# Micro_RC_Transmitter.net
KiCad netlist of a schematic drawn in EAGLE
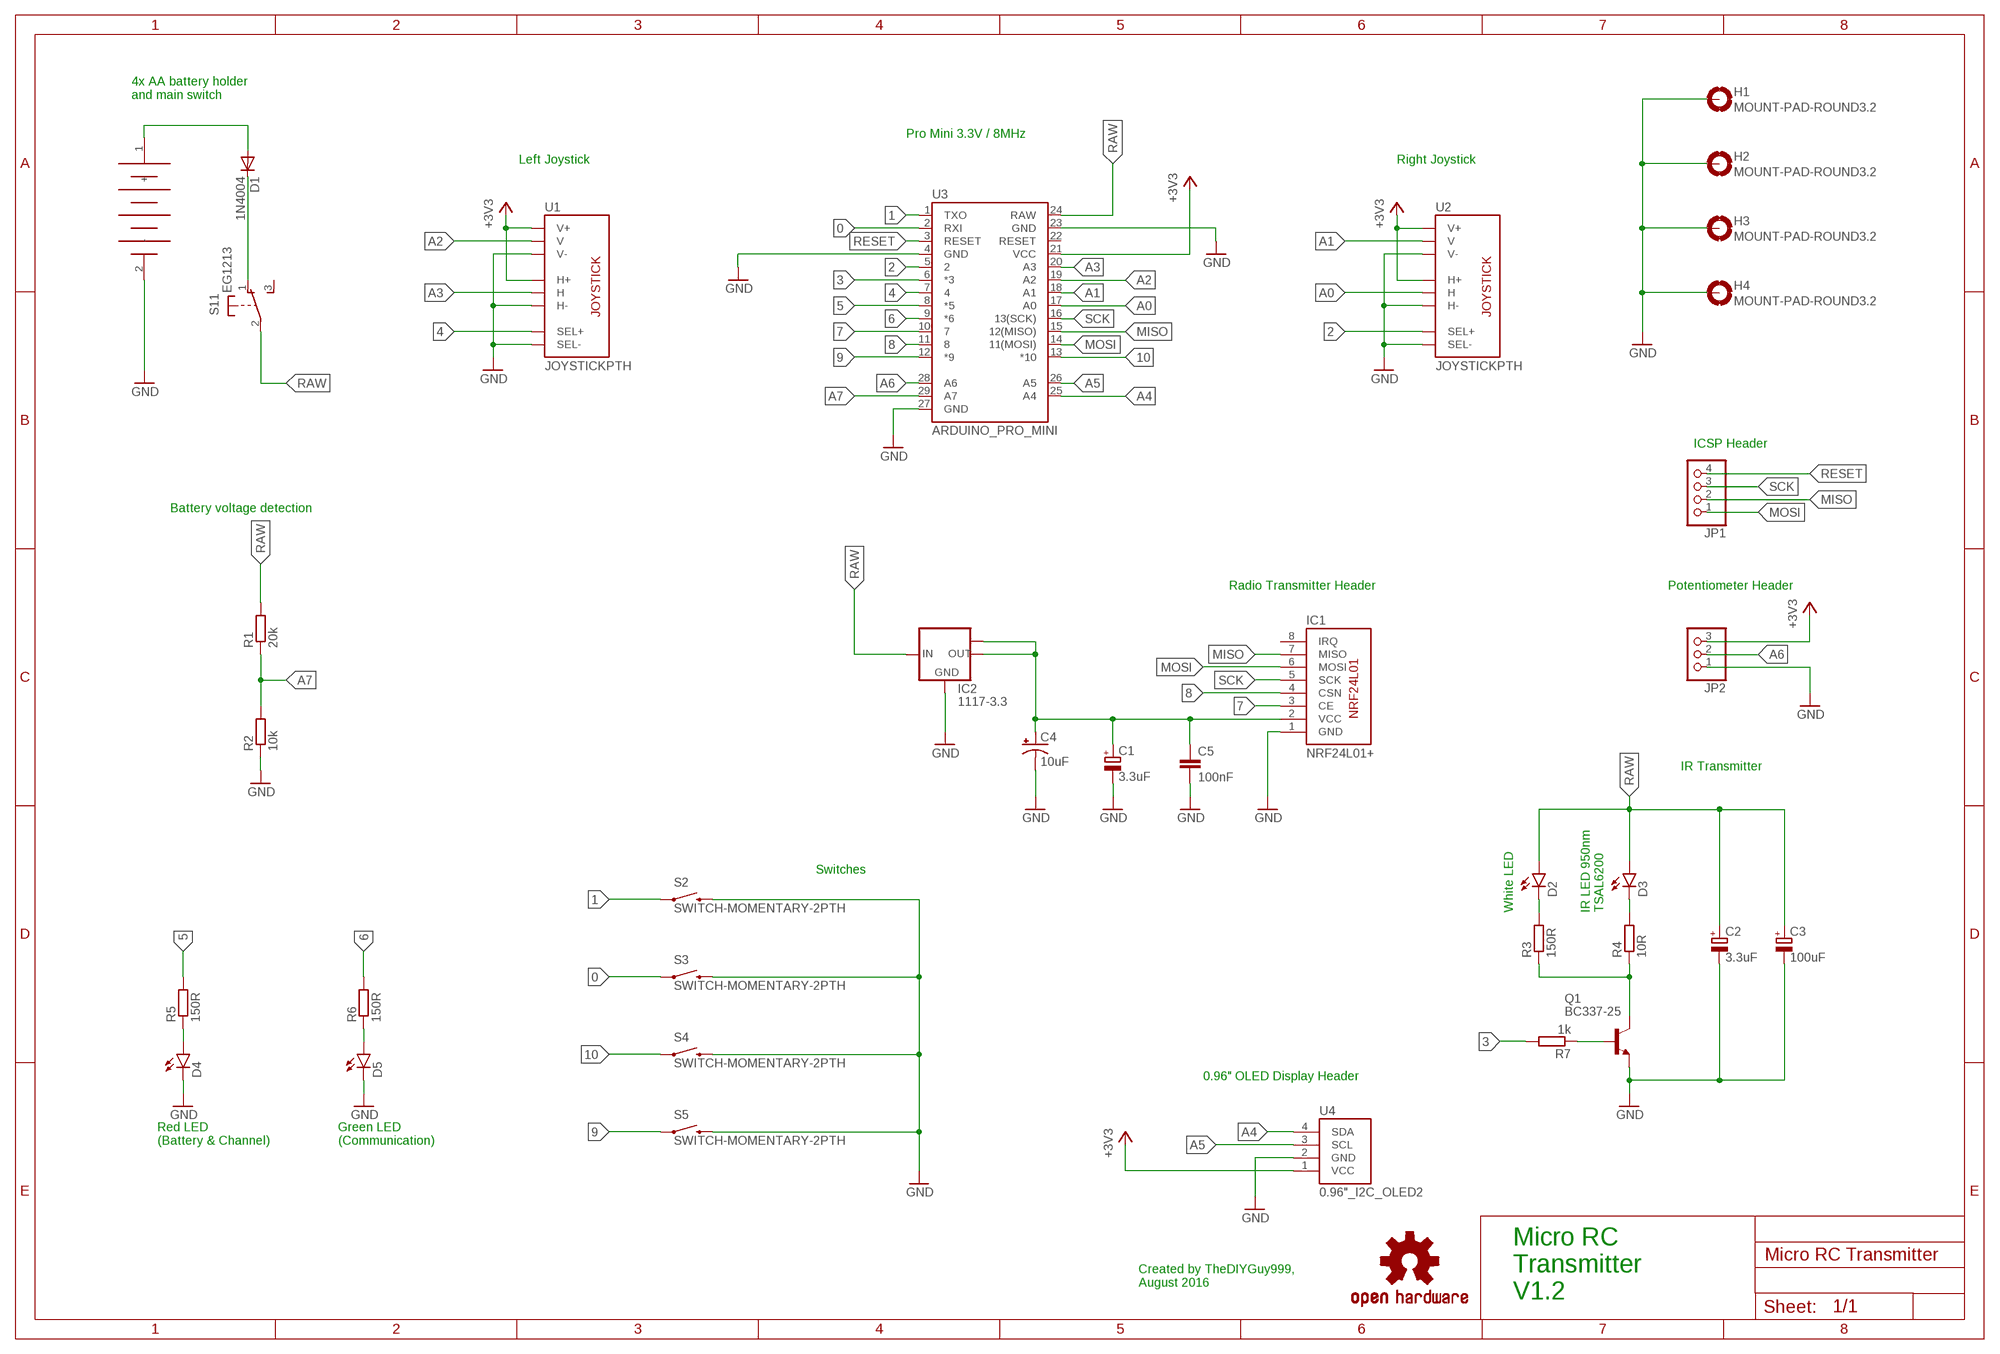
[diagram p0: schematic, sheet 1]

(export (version "E")
  (design (tool "Eeschema 10.0.6"))
  (components
    (comp (ref "C1")
      (value "3.3uF")
      (footprint "eagle-import:B45181A")
      (libsource (lib "eagle-import") (part "CPOL-EUB45181A"))
    )
    (comp (ref "C2")
      (value "3.3uF")
      (footprint "eagle-import:B45181A")
      (libsource (lib "eagle-import") (part "CPOL-EUB45181A"))
    )
    (comp (ref "C3")
      (value "100uF")
      (footprint "eagle-import:E2,5-7")
      (libsource (lib "eagle-import") (part "CPOL-EUE2.5-7"))
    )
    (comp (ref "C4")
      (value "10uF")
      (footprint "eagle-import:EIA3216")
      (libsource (lib "eagle-import") (part "10UF-16V-10%(TANT)"))
    )
    (comp (ref "C5")
      (value "100nF")
      (footprint "eagle-import:C0805")
      (libsource (lib "eagle-import") (part "C-EUC0805"))
    )
    (comp (ref "D1")
      (value "1N4004")
      (footprint "eagle-import:DO41-10")
      (libsource (lib "eagle-import") (part "1N4004"))
    )
    (comp (ref "D2")
      (value "LED5MM")
      (footprint "eagle-import:LED5MM")
      (libsource (lib "eagle-import") (part "LED5MM"))
    )
    (comp (ref "D3")
      (value "LED5MM")
      (footprint "eagle-import:LED5MM")
      (libsource (lib "eagle-import") (part "LED5MM"))
    )
    (comp (ref "D4")
      (value "LED3MM")
      (footprint "eagle-import:LED3MM")
      (libsource (lib "eagle-import") (part "LED3MM"))
    )
    (comp (ref "D5")
      (value "LED3MM")
      (footprint "eagle-import:LED3MM")
      (libsource (lib "eagle-import") (part "LED3MM"))
    )
    (comp (ref "G1")
      (value "4X_AA_BATTERY_HOLDER")
      (footprint "eagle-import:4X_AA_BATTERY_HOLDER")
      (libsource (lib "eagle-import") (part "4X_AA_BATTERY_HOLDER"))
    )
    (comp (ref "H1")
      (value "MOUNT-PAD-ROUND3.2")
      (footprint "eagle-import:3,2-PAD")
      (libsource (lib "eagle-import") (part "MOUNT-PAD-ROUND3.2"))
    )
    (comp (ref "H2")
      (value "MOUNT-PAD-ROUND3.2")
      (footprint "eagle-import:3,2-PAD")
      (libsource (lib "eagle-import") (part "MOUNT-PAD-ROUND3.2"))
    )
    (comp (ref "H3")
      (value "MOUNT-PAD-ROUND3.2")
      (footprint "eagle-import:3,2-PAD")
      (libsource (lib "eagle-import") (part "MOUNT-PAD-ROUND3.2"))
    )
    (comp (ref "H4")
      (value "MOUNT-PAD-ROUND3.2")
      (footprint "eagle-import:3,2-PAD")
      (libsource (lib "eagle-import") (part "MOUNT-PAD-ROUND3.2"))
    )
    (comp (ref "IC1")
      (value "NRF24L01+")
      (footprint "eagle-import:NRF24L01")
      (libsource (lib "eagle-import") (part "NRF24L01"))
    )
    (comp (ref "IC2")
      (value "1117-3.3")
      (footprint "eagle-import:SOT223")
      (libsource (lib "eagle-import") (part "LM1117MPX-3.3"))
    )
    (comp (ref "JP1")
      (value "PINHD-1X4")
      (footprint "eagle-import:1X04")
      (libsource (lib "eagle-import") (part "PINHD-1X4"))
    )
    (comp (ref "JP2")
      (value "PINHD-1X3")
      (footprint "eagle-import:1X03")
      (libsource (lib "eagle-import") (part "PINHD-1X3"))
    )
    (comp (ref "LOGO1")
      (value "OSHW-LOGOM")
      (footprint "eagle-import:OSHW-LOGO-M")
      (libsource (lib "eagle-import") (part "OSHW-LOGOM"))
    )
    (comp (ref "Q1")
      (value "BC337-25")
      (footprint "eagle-import:TO92")
      (libsource (lib "eagle-import") (part "BC337-25"))
    )
    (comp (ref "R1")
      (value "20k")
      (footprint "eagle-import:0207_10")
      (libsource (lib "eagle-import") (part "R-EU_0207/10"))
    )
    (comp (ref "R2")
      (value "10k")
      (footprint "eagle-import:0207_10")
      (libsource (lib "eagle-import") (part "R-EU_0207/10"))
    )
    (comp (ref "R3")
      (value "150R")
      (footprint "eagle-import:0207_10")
      (libsource (lib "eagle-import") (part "R-EU_0207/10"))
    )
    (comp (ref "R4")
      (value "10R")
      (footprint "eagle-import:0207_10")
      (libsource (lib "eagle-import") (part "R-EU_0207/10"))
    )
    (comp (ref "R5")
      (value "150R")
      (footprint "eagle-import:0207_10")
      (libsource (lib "eagle-import") (part "R-EU_0207/10"))
    )
    (comp (ref "R6")
      (value "150R")
      (footprint "eagle-import:0207_10")
      (libsource (lib "eagle-import") (part "R-EU_0207/10"))
    )
    (comp (ref "R7")
      (value "1k")
      (footprint "eagle-import:0207_10")
      (libsource (lib "eagle-import") (part "R-EU_0207/10"))
    )
    (comp (ref "S1")
      (value "EG1213")
      (footprint "eagle-import:EG1213")
      (libsource (lib "eagle-import") (part "EG1213"))
    )
    (comp (ref "S2")
      (value "SWITCH-MOMENTARY-2PTH")
      (footprint "eagle-import:TACTILE-PTH")
      (libsource (lib "eagle-import") (part "SWITCH-MOMENTARY-2PTH"))
    )
    (comp (ref "S3")
      (value "SWITCH-MOMENTARY-2PTH")
      (footprint "eagle-import:TACTILE-PTH")
      (libsource (lib "eagle-import") (part "SWITCH-MOMENTARY-2PTH"))
    )
    (comp (ref "S4")
      (value "SWITCH-MOMENTARY-2PTH")
      (footprint "eagle-import:TACTILE-PTH")
      (libsource (lib "eagle-import") (part "SWITCH-MOMENTARY-2PTH"))
    )
    (comp (ref "S5")
      (value "SWITCH-MOMENTARY-2PTH")
      (footprint "eagle-import:TACTILE-PTH")
      (libsource (lib "eagle-import") (part "SWITCH-MOMENTARY-2PTH"))
    )
    (comp (ref "U1")
      (value "JOYSTICKPTH")
      (footprint "eagle-import:JOYSTICK")
      (libsource (lib "eagle-import") (part "JOYSTICKPTH"))
    )
    (comp (ref "U2")
      (value "JOYSTICKPTH")
      (footprint "eagle-import:JOYSTICK")
      (libsource (lib "eagle-import") (part "JOYSTICKPTH"))
    )
    (comp (ref "U3")
      (value "ARDUINO_PRO_MINI")
      (footprint "eagle-import:ARDUINO_PRO_MINI")
      (libsource (lib "eagle-import") (part "ARDUINO_PRO_MINI"))
    )
    (comp (ref "U4")
      (value "0.96\"_I2C_OLED2")
      (footprint "eagle-import:0.96__I2C_OLED_2")
      (libsource (lib "eagle-import") (part "0.96{dblquote}_I2C_OLED2"))
    )
  )
  (nets
    (net (code "1") (name "+3V3") (class "Default")
      (node (ref "JP2") (pin "3") (pinfunction "3_3") (pintype "passive"))
      (node (ref "U1") (pin "H1") (pinfunction "H+_H1") (pintype "bidirectional"))
      (node (ref "U1") (pin "V1") (pinfunction "V+_V1") (pintype "bidirectional"))
      (node (ref "U2") (pin "H1") (pinfunction "H+_H1") (pintype "bidirectional"))
      (node (ref "U2") (pin "V1") (pinfunction "V+_V1") (pintype "bidirectional"))
      (node (ref "U3") (pin "21") (pinfunction "VCC_21") (pintype "bidirectional"))
      (node (ref "U4") (pin "1") (pinfunction "VCC_1") (pintype "bidirectional"))
    )
    (net (code "2") (name "0") (class "Default")
      (node (ref "S3") (pin "1") (pinfunction "1_1") (pintype "passive"))
      (node (ref "U3") (pin "2") (pinfunction "RXI_2") (pintype "bidirectional"))
    )
    (net (code "3") (name "1") (class "Default")
      (node (ref "S2") (pin "1") (pinfunction "1_1") (pintype "passive"))
      (node (ref "U3") (pin "1") (pinfunction "TXO_1") (pintype "bidirectional"))
    )
    (net (code "4") (name "2") (class "Default")
      (node (ref "U2") (pin "B1A") (pinfunction "SEL+_B1A") (pintype "bidirectional"))
      (node (ref "U3") (pin "5") (pinfunction "2_5") (pintype "bidirectional"))
    )
    (net (code "5") (name "3") (class "Default")
      (node (ref "R7") (pin "2") (pinfunction "2_2") (pintype "passive"))
      (node (ref "U3") (pin "6") (pinfunction "*3_6") (pintype "bidirectional"))
    )
    (net (code "6") (name "4") (class "Default")
      (node (ref "U1") (pin "B1A") (pinfunction "SEL+_B1A") (pintype "bidirectional"))
      (node (ref "U3") (pin "7") (pinfunction "4_7") (pintype "bidirectional"))
    )
    (net (code "7") (name "5") (class "Default")
      (node (ref "R5") (pin "2") (pinfunction "2_2") (pintype "passive"))
      (node (ref "U3") (pin "8") (pinfunction "*5_8") (pintype "bidirectional"))
    )
    (net (code "8") (name "6") (class "Default")
      (node (ref "R6") (pin "2") (pinfunction "2_2") (pintype "passive"))
      (node (ref "U3") (pin "9") (pinfunction "*6_9") (pintype "bidirectional"))
    )
    (net (code "9") (name "7") (class "Default")
      (node (ref "IC1") (pin "3") (pinfunction "CE_3") (pintype "bidirectional"))
      (node (ref "U3") (pin "10") (pinfunction "7_10") (pintype "bidirectional"))
    )
    (net (code "10") (name "8") (class "Default")
      (node (ref "IC1") (pin "4") (pinfunction "CSN_4") (pintype "bidirectional"))
      (node (ref "U3") (pin "11") (pinfunction "8_11") (pintype "bidirectional"))
    )
    (net (code "11") (name "9") (class "Default")
      (node (ref "S5") (pin "1") (pinfunction "1_1") (pintype "passive"))
      (node (ref "U3") (pin "12") (pinfunction "*9_12") (pintype "bidirectional"))
    )
    (net (code "12") (name "10") (class "Default")
      (node (ref "S4") (pin "1") (pinfunction "1_1") (pintype "passive"))
      (node (ref "U3") (pin "13") (pinfunction "*10_13") (pintype "bidirectional"))
    )
    (net (code "13") (name "A0") (class "Default")
      (node (ref "U2") (pin "H2") (pinfunction "H_H2") (pintype "bidirectional"))
      (node (ref "U3") (pin "17") (pinfunction "A0_17") (pintype "bidirectional"))
    )
    (net (code "14") (name "A1") (class "Default")
      (node (ref "U2") (pin "V2") (pinfunction "V_V2") (pintype "bidirectional"))
      (node (ref "U3") (pin "18") (pinfunction "A1_18") (pintype "bidirectional"))
    )
    (net (code "15") (name "A2") (class "Default")
      (node (ref "U1") (pin "V2") (pinfunction "V_V2") (pintype "bidirectional"))
      (node (ref "U3") (pin "19") (pinfunction "A2_19") (pintype "bidirectional"))
    )
    (net (code "16") (name "A3") (class "Default")
      (node (ref "U1") (pin "H2") (pinfunction "H_H2") (pintype "bidirectional"))
      (node (ref "U3") (pin "20") (pinfunction "A3_20") (pintype "bidirectional"))
    )
    (net (code "17") (name "A4") (class "Default")
      (node (ref "U3") (pin "25") (pinfunction "A4_25") (pintype "bidirectional"))
      (node (ref "U4") (pin "4") (pinfunction "SDA_4") (pintype "bidirectional"))
    )
    (net (code "18") (name "A5") (class "Default")
      (node (ref "U3") (pin "26") (pinfunction "A5_26") (pintype "bidirectional"))
      (node (ref "U4") (pin "3") (pinfunction "SCL_3") (pintype "bidirectional"))
    )
    (net (code "19") (name "A6") (class "Default")
      (node (ref "JP2") (pin "2") (pinfunction "2_2") (pintype "passive"))
      (node (ref "U3") (pin "28") (pinfunction "A6_28") (pintype "bidirectional"))
    )
    (net (code "20") (name "A7") (class "Default")
      (node (ref "R1") (pin "1") (pinfunction "1_1") (pintype "passive"))
      (node (ref "R2") (pin "2") (pinfunction "2_2") (pintype "passive"))
      (node (ref "U3") (pin "29") (pinfunction "A7_29") (pintype "bidirectional"))
    )
    (net (code "21") (name "GND") (class "Default")
      (node (ref "C1") (pin "-") (pinfunction "-_-") (pintype "passive"))
      (node (ref "C2") (pin "-") (pinfunction "-_-") (pintype "passive"))
      (node (ref "C3") (pin "-") (pinfunction "-_-") (pintype "passive"))
      (node (ref "C4") (pin "C") (pinfunction "-_C") (pintype "passive"))
      (node (ref "C5") (pin "2") (pinfunction "2_2") (pintype "passive"))
      (node (ref "D4") (pin "K") (pinfunction "C_K") (pintype "passive"))
      (node (ref "D5") (pin "K") (pinfunction "C_K") (pintype "passive"))
      (node (ref "G1") (pin "2") (pinfunction "-_2") (pintype "bidirectional"))
      (node (ref "H1") (pin "B3,2") (pinfunction "MOUNT_B3,2") (pintype "passive"))
      (node (ref "H2") (pin "B3,2") (pinfunction "MOUNT_B3,2") (pintype "passive"))
      (node (ref "H3") (pin "B3,2") (pinfunction "MOUNT_B3,2") (pintype "passive"))
      (node (ref "H4") (pin "B3,2") (pinfunction "MOUNT_B3,2") (pintype "passive"))
      (node (ref "IC1") (pin "1") (pinfunction "GND_1") (pintype "bidirectional"))
      (node (ref "IC2") (pin "1") (pinfunction "GND_1") (pintype "input"))
      (node (ref "JP2") (pin "1") (pinfunction "1_1") (pintype "passive"))
      (node (ref "Q1") (pin "1") (pinfunction "E_1") (pintype "passive"))
      (node (ref "R2") (pin "1") (pinfunction "1_1") (pintype "passive"))
      (node (ref "S2") (pin "3") (pinfunction "2_3") (pintype "passive"))
      (node (ref "S3") (pin "3") (pinfunction "2_3") (pintype "passive"))
      (node (ref "S4") (pin "3") (pinfunction "2_3") (pintype "passive"))
      (node (ref "S5") (pin "3") (pinfunction "2_3") (pintype "passive"))
      (node (ref "U1") (pin "B2A") (pinfunction "SEL-_B2A") (pintype "bidirectional"))
      (node (ref "U1") (pin "H3") (pinfunction "H-_H3") (pintype "bidirectional"))
      (node (ref "U1") (pin "V3") (pinfunction "V-_V3") (pintype "bidirectional"))
      (node (ref "U2") (pin "B2A") (pinfunction "SEL-_B2A") (pintype "bidirectional"))
      (node (ref "U2") (pin "H3") (pinfunction "H-_H3") (pintype "bidirectional"))
      (node (ref "U2") (pin "V3") (pinfunction "V-_V3") (pintype "bidirectional"))
      (node (ref "U3") (pin "23") (pinfunction "GND_23") (pintype "bidirectional"))
      (node (ref "U3") (pin "27") (pinfunction "GND_27") (pintype "bidirectional"))
      (node (ref "U3") (pin "4") (pinfunction "GND_4") (pintype "bidirectional"))
      (node (ref "U4") (pin "2") (pinfunction "GND_2") (pintype "bidirectional"))
    )
    (net (code "22") (name "MISO") (class "Default")
      (node (ref "IC1") (pin "7") (pinfunction "MISO_7") (pintype "bidirectional"))
      (node (ref "JP1") (pin "2") (pinfunction "2_2") (pintype "passive"))
      (node (ref "U3") (pin "15") (pinfunction "12(MISO)_15") (pintype "bidirectional"))
    )
    (net (code "23") (name "MOSI") (class "Default")
      (node (ref "IC1") (pin "6") (pinfunction "MOSI_6") (pintype "bidirectional"))
      (node (ref "JP1") (pin "1") (pinfunction "1_1") (pintype "passive"))
      (node (ref "U3") (pin "14") (pinfunction "11(MOSI)_14") (pintype "bidirectional"))
    )
    (net (code "24") (name "Net-(C4-+)") (class "Default")
      (node (ref "C1") (pin "+") (pinfunction "+_+") (pintype "passive"))
      (node (ref "C4") (pin "A") (pinfunction "+_A") (pintype "passive"))
      (node (ref "C5") (pin "1") (pinfunction "1_1") (pintype "passive"))
      (node (ref "IC1") (pin "2") (pinfunction "VCC_2") (pintype "bidirectional"))
      (node (ref "IC2") (pin "2") (pinfunction "OUT_2") (pintype "passive"))
      (node (ref "IC2") (pin "TAB") (pinfunction "OUT1_TAB") (pintype "passive"))
    )
    (net (code "25") (name "Net-(D2-C)") (class "Default")
      (node (ref "D2") (pin "K") (pinfunction "C_K") (pintype "passive"))
      (node (ref "R3") (pin "2") (pinfunction "2_2") (pintype "passive"))
    )
    (net (code "26") (name "Net-(D3-C)") (class "Default")
      (node (ref "D3") (pin "K") (pinfunction "C_K") (pintype "passive"))
      (node (ref "R4") (pin "2") (pinfunction "2_2") (pintype "passive"))
    )
    (net (code "27") (name "Net-(D4-PadA)") (class "Default")
      (node (ref "D4") (pin "A") (pinfunction "A_A") (pintype "passive"))
      (node (ref "R5") (pin "1") (pinfunction "1_1") (pintype "passive"))
    )
    (net (code "28") (name "Net-(D5-PadA)") (class "Default")
      (node (ref "D5") (pin "A") (pinfunction "A_A") (pintype "passive"))
      (node (ref "R6") (pin "1") (pinfunction "1_1") (pintype "passive"))
    )
    (net (code "29") (name "Net-(G1-+)") (class "Default")
      (node (ref "D1") (pin "A") (pinfunction "A_A") (pintype "passive"))
      (node (ref "G1") (pin "1") (pinfunction "+_1") (pintype "bidirectional"))
    )
    (net (code "30") (name "Net-(Q1-B)") (class "Default")
      (node (ref "Q1") (pin "2") (pinfunction "B_2") (pintype "passive"))
      (node (ref "R7") (pin "1") (pinfunction "1_1") (pintype "passive"))
    )
    (net (code "31") (name "Net-(Q1-C)") (class "Default")
      (node (ref "Q1") (pin "3") (pinfunction "C_3") (pintype "passive"))
      (node (ref "R3") (pin "1") (pinfunction "1_1") (pintype "passive"))
      (node (ref "R4") (pin "1") (pinfunction "1_1") (pintype "passive"))
    )
    (net (code "32") (name "Net-(S1A-O)") (class "Default")
      (node (ref "D1") (pin "C") (pinfunction "C_C") (pintype "passive"))
      (node (ref "S1") (pin "1") (pinfunction "O_1") (pintype "passive"))
    )
    (net (code "33") (name "RAW") (class "Default")
      (node (ref "C2") (pin "+") (pinfunction "+_+") (pintype "passive"))
      (node (ref "C3") (pin "+") (pinfunction "+_+") (pintype "passive"))
      (node (ref "D2") (pin "A") (pinfunction "A_A") (pintype "passive"))
      (node (ref "D3") (pin "A") (pinfunction "A_A") (pintype "passive"))
      (node (ref "IC2") (pin "3") (pinfunction "IN_3") (pintype "input"))
      (node (ref "R1") (pin "2") (pinfunction "2_2") (pintype "passive"))
      (node (ref "S1") (pin "2") (pinfunction "P_2") (pintype "passive"))
      (node (ref "U3") (pin "24") (pinfunction "RAW_24") (pintype "bidirectional"))
    )
    (net (code "34") (name "RESET") (class "Default")
      (node (ref "JP1") (pin "4") (pinfunction "4_4") (pintype "passive"))
      (node (ref "U3") (pin "3") (pinfunction "RESET_3") (pintype "bidirectional"))
    )
    (net (code "35") (name "SCK") (class "Default")
      (node (ref "IC1") (pin "5") (pinfunction "SCK_5") (pintype "bidirectional"))
      (node (ref "JP1") (pin "3") (pinfunction "3_3") (pintype "passive"))
      (node (ref "U3") (pin "16") (pinfunction "13(SCK)_16") (pintype "bidirectional"))
    )
    (net (code "36") (name "unconnected-(IC1-IRQ-Pad8)") (class "Default")
      (node (ref "IC1") (pin "8") (pinfunction "IRQ_8") (pintype "bidirectional"))
    )
    (net (code "37") (name "unconnected-(S1A-S-Pad3)") (class "Default")
      (node (ref "S1") (pin "3") (pinfunction "S_3") (pintype "passive"))
    )
    (net (code "38") (name "unconnected-(U3-RESET-Pad22)") (class "Default")
      (node (ref "U3") (pin "22") (pinfunction "RESET_22") (pintype "bidirectional"))
    )
  )
)
